# BattleBits_V2_routed.net
KiCad netlist of a schematic drawn in EAGLE
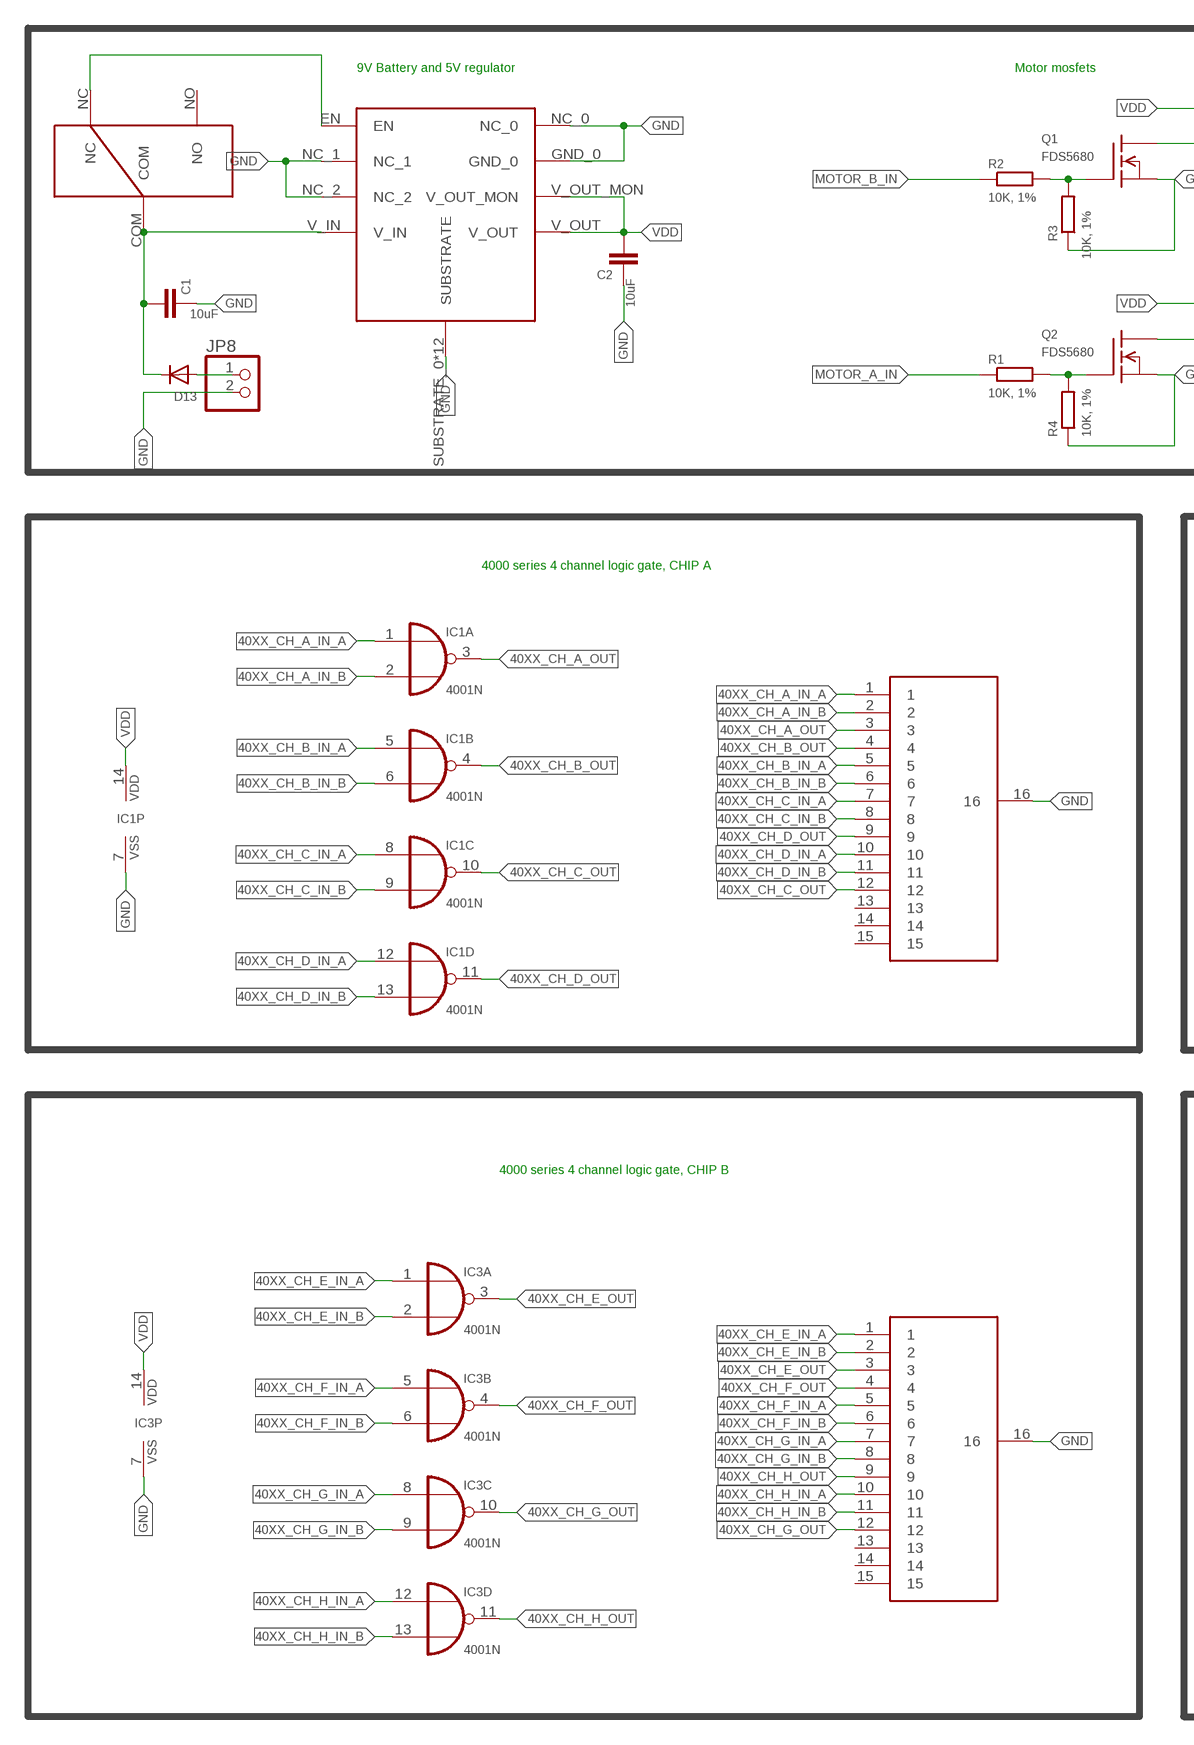
[diagram p0: schematic, sheet 1, part 1 of 2]
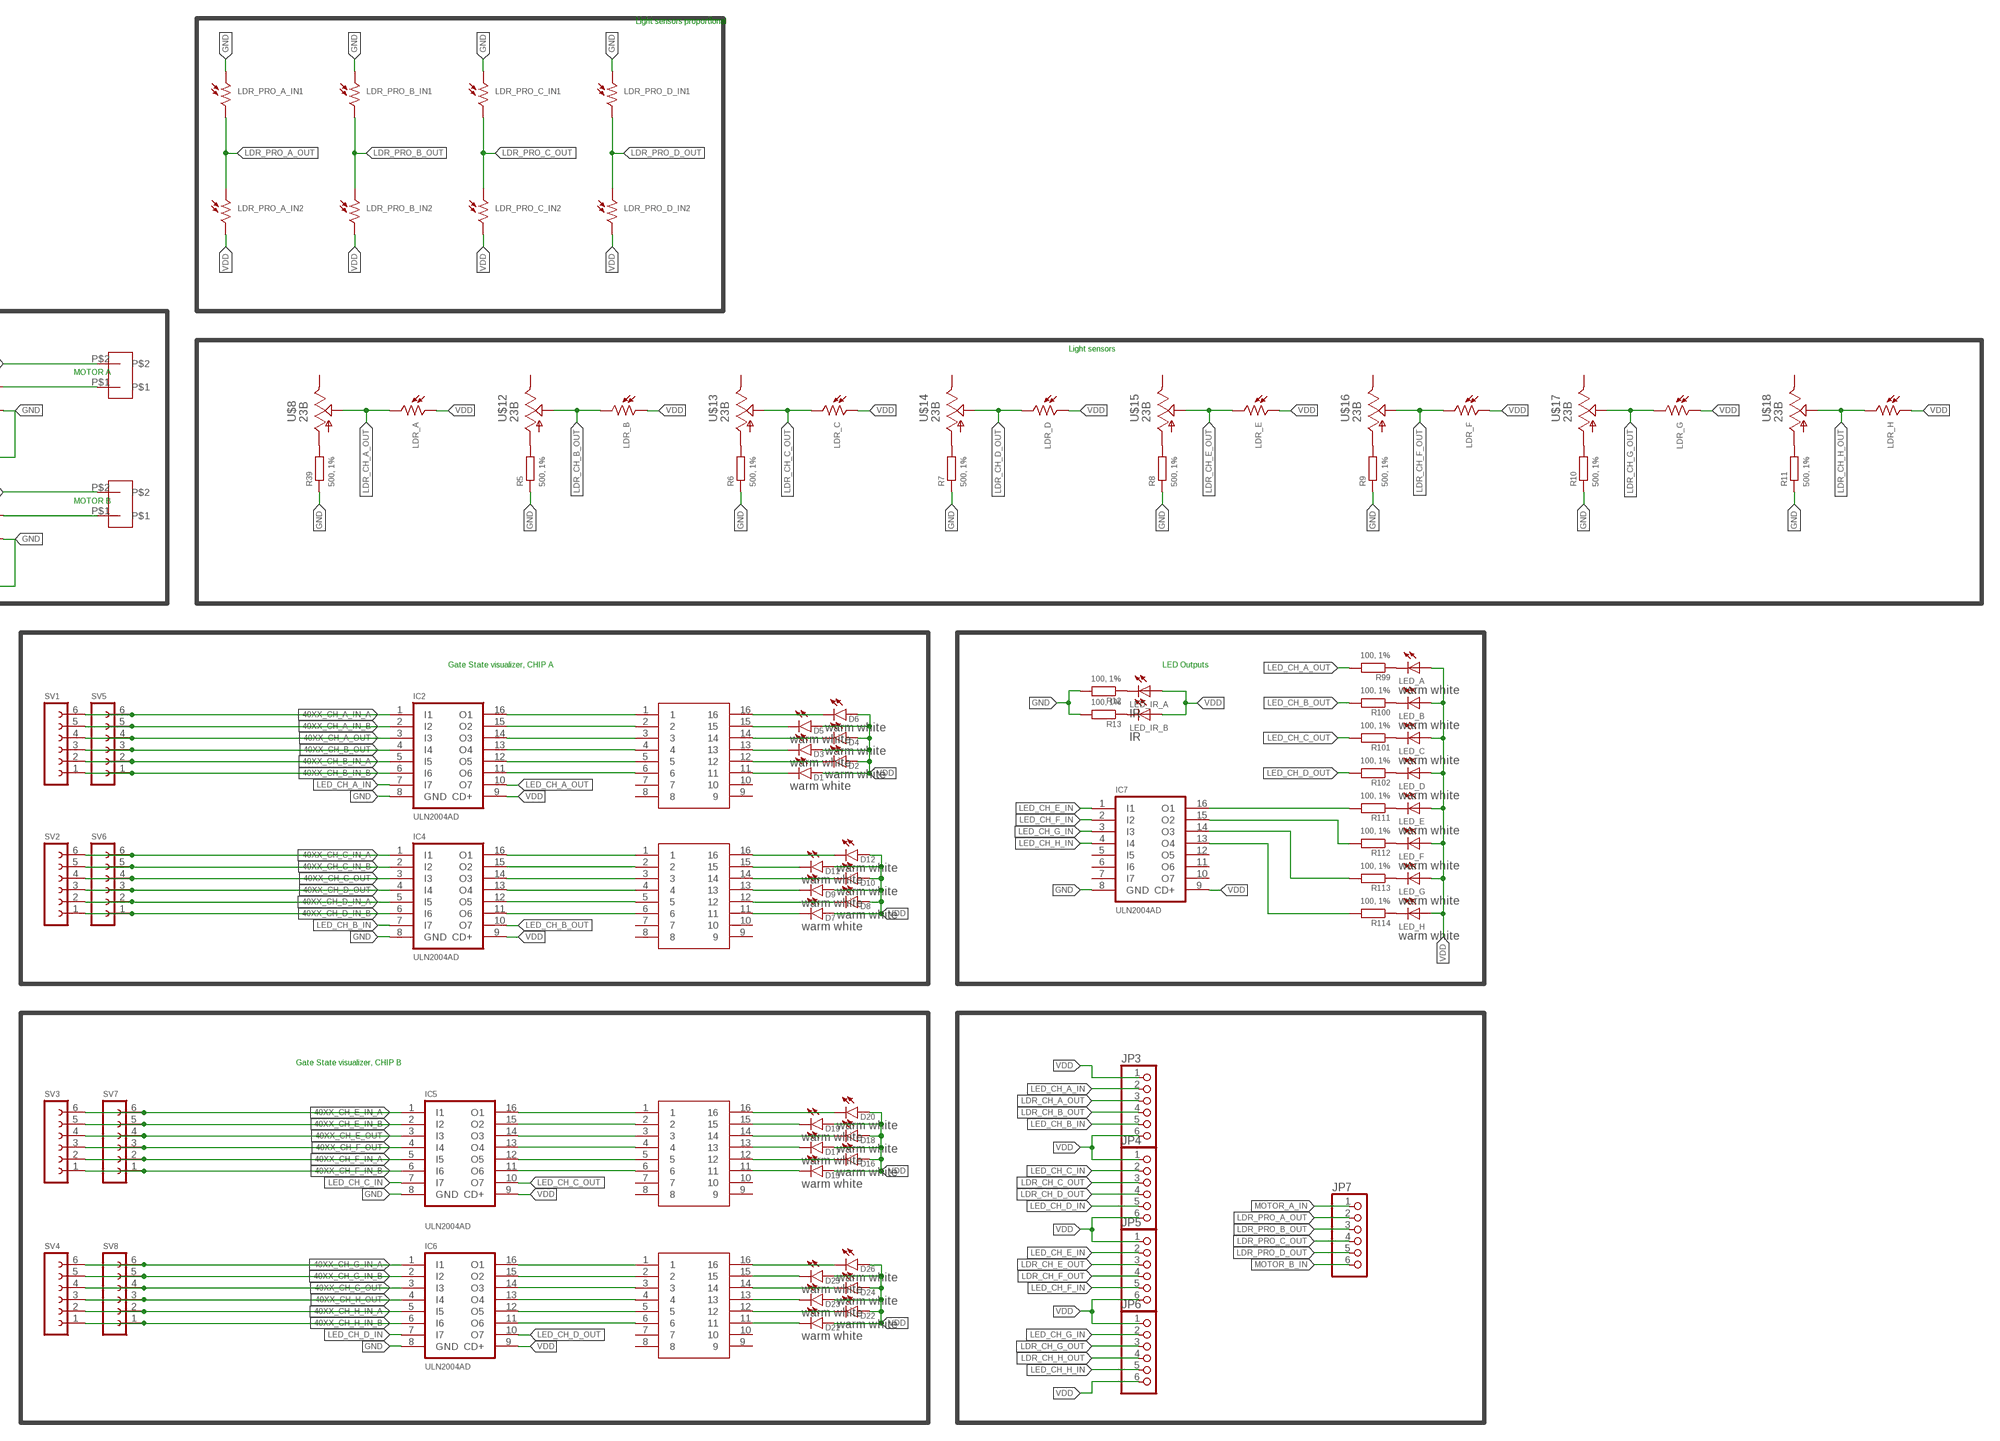
[diagram p1: schematic, sheet 1, part 2 of 2]

(export (version "E")
  (design (tool "Eeschema 10.0.6"))
  (components
    (comp (ref "C1")
      (value "10uF")
      (footprint "eagle-import:C3216")
      (libsource (lib "eagle-import") (part "C-EUC3216"))
    )
    (comp (ref "C2")
      (value "10uF")
      (footprint "eagle-import:C3216")
      (libsource (lib "eagle-import") (part "C-EUC3216"))
    )
    (comp (ref "D1")
      (value "warm white")
      (footprint "eagle-import:LED-1206")
      (libsource (lib "eagle-import") (part "LED1206"))
    )
    (comp (ref "D2")
      (value "warm white")
      (footprint "eagle-import:LED-1206")
      (libsource (lib "eagle-import") (part "LED1206"))
    )
    (comp (ref "D3")
      (value "warm white")
      (footprint "eagle-import:LED-1206")
      (libsource (lib "eagle-import") (part "LED1206"))
    )
    (comp (ref "D4")
      (value "warm white")
      (footprint "eagle-import:LED-1206")
      (libsource (lib "eagle-import") (part "LED1206"))
    )
    (comp (ref "D5")
      (value "warm white")
      (footprint "eagle-import:LED-1206")
      (libsource (lib "eagle-import") (part "LED1206"))
    )
    (comp (ref "D6")
      (value "warm white")
      (footprint "eagle-import:LED-1206")
      (libsource (lib "eagle-import") (part "LED1206"))
    )
    (comp (ref "D7")
      (value "warm white")
      (footprint "eagle-import:LED-1206")
      (libsource (lib "eagle-import") (part "LED1206"))
    )
    (comp (ref "D8")
      (value "warm white")
      (footprint "eagle-import:LED-1206")
      (libsource (lib "eagle-import") (part "LED1206"))
    )
    (comp (ref "D9")
      (value "warm white")
      (footprint "eagle-import:LED-1206")
      (libsource (lib "eagle-import") (part "LED1206"))
    )
    (comp (ref "D10")
      (value "warm white")
      (footprint "eagle-import:LED-1206")
      (libsource (lib "eagle-import") (part "LED1206"))
    )
    (comp (ref "D11")
      (value "warm white")
      (footprint "eagle-import:LED-1206")
      (libsource (lib "eagle-import") (part "LED1206"))
    )
    (comp (ref "D12")
      (value "warm white")
      (footprint "eagle-import:LED-1206")
      (libsource (lib "eagle-import") (part "LED1206"))
    )
    (comp (ref "D13")
      (value "DIODESMA")
      (footprint "eagle-import:SMADIODE")
      (libsource (lib "eagle-import") (part "DIODESMA"))
    )
    (comp (ref "D15")
      (value "warm white")
      (footprint "eagle-import:LED-1206")
      (libsource (lib "eagle-import") (part "LED1206"))
    )
    (comp (ref "D16")
      (value "warm white")
      (footprint "eagle-import:LED-1206")
      (libsource (lib "eagle-import") (part "LED1206"))
    )
    (comp (ref "D17")
      (value "warm white")
      (footprint "eagle-import:LED-1206")
      (libsource (lib "eagle-import") (part "LED1206"))
    )
    (comp (ref "D18")
      (value "warm white")
      (footprint "eagle-import:LED-1206")
      (libsource (lib "eagle-import") (part "LED1206"))
    )
    (comp (ref "D19")
      (value "warm white")
      (footprint "eagle-import:LED-1206")
      (libsource (lib "eagle-import") (part "LED1206"))
    )
    (comp (ref "D20")
      (value "warm white")
      (footprint "eagle-import:LED-1206")
      (libsource (lib "eagle-import") (part "LED1206"))
    )
    (comp (ref "D21")
      (value "warm white")
      (footprint "eagle-import:LED-1206")
      (libsource (lib "eagle-import") (part "LED1206"))
    )
    (comp (ref "D22")
      (value "warm white")
      (footprint "eagle-import:LED-1206")
      (libsource (lib "eagle-import") (part "LED1206"))
    )
    (comp (ref "D23")
      (value "warm white")
      (footprint "eagle-import:LED-1206")
      (libsource (lib "eagle-import") (part "LED1206"))
    )
    (comp (ref "D24")
      (value "warm white")
      (footprint "eagle-import:LED-1206")
      (libsource (lib "eagle-import") (part "LED1206"))
    )
    (comp (ref "D25")
      (value "warm white")
      (footprint "eagle-import:LED-1206")
      (libsource (lib "eagle-import") (part "LED1206"))
    )
    (comp (ref "D26")
      (value "warm white")
      (footprint "eagle-import:LED-1206")
      (libsource (lib "eagle-import") (part "LED1206"))
    )
    (comp (ref "IC1")
      (value "4001N")
      (footprint "eagle-import:DIL14")
      (libsource (lib "eagle-import") (part "4001N"))
    )
    (comp (ref "IC2")
      (value "ULN2004AD")
      (footprint "eagle-import:SO16")
      (libsource (lib "eagle-import") (part "ULN2004AD"))
    )
    (comp (ref "IC3")
      (value "4001N")
      (footprint "eagle-import:DIL14")
      (libsource (lib "eagle-import") (part "4001N"))
    )
    (comp (ref "IC4")
      (value "ULN2004AD")
      (footprint "eagle-import:SO16")
      (libsource (lib "eagle-import") (part "ULN2004AD"))
    )
    (comp (ref "IC5")
      (value "ULN2004AD")
      (footprint "eagle-import:SO16")
      (libsource (lib "eagle-import") (part "ULN2004AD"))
    )
    (comp (ref "IC6")
      (value "ULN2004AD")
      (footprint "eagle-import:SO16")
      (libsource (lib "eagle-import") (part "ULN2004AD"))
    )
    (comp (ref "IC7")
      (value "ULN2004AD")
      (footprint "eagle-import:SO16")
      (libsource (lib "eagle-import") (part "ULN2004AD"))
    )
    (comp (ref "JP3")
      (value "PINHD-1X6")
      (footprint "eagle-import:1X06")
      (libsource (lib "eagle-import") (part "PINHD-1X6"))
    )
    (comp (ref "JP4")
      (value "PINHD-1X6")
      (footprint "eagle-import:1X06")
      (libsource (lib "eagle-import") (part "PINHD-1X6"))
    )
    (comp (ref "JP5")
      (value "PINHD-1X6")
      (footprint "eagle-import:1X06")
      (libsource (lib "eagle-import") (part "PINHD-1X6"))
    )
    (comp (ref "JP6")
      (value "PINHD-1X6")
      (footprint "eagle-import:1X06")
      (libsource (lib "eagle-import") (part "PINHD-1X6"))
    )
    (comp (ref "JP7")
      (value "PINHD-1X6")
      (footprint "eagle-import:1X06")
      (libsource (lib "eagle-import") (part "PINHD-1X6"))
    )
    (comp (ref "JP8")
      (value "PINHD-1X2")
      (footprint "eagle-import:1X02")
      (libsource (lib "eagle-import") (part "PINHD-1X2"))
    )
    (comp (ref "LDR_A")
      (value "V1060_21")
      (footprint "eagle-import:TO-5_V10")
      (libsource (lib "eagle-import") (part "?1060V_21"))
    )
    (comp (ref "LDR_B")
      (value "V1060_21")
      (footprint "eagle-import:TO-5_V10")
      (libsource (lib "eagle-import") (part "?1060V_21"))
    )
    (comp (ref "LDR_C")
      (value "V1060_21")
      (footprint "eagle-import:TO-5_V10")
      (libsource (lib "eagle-import") (part "?1060V_21"))
    )
    (comp (ref "LDR_D")
      (value "V1060_21")
      (footprint "eagle-import:TO-5_V10")
      (libsource (lib "eagle-import") (part "?1060V_21"))
    )
    (comp (ref "LDR_E")
      (value "V1060_21")
      (footprint "eagle-import:TO-5_V10")
      (libsource (lib "eagle-import") (part "?1060V_21"))
    )
    (comp (ref "LDR_F")
      (value "V1060_21")
      (footprint "eagle-import:TO-5_V10")
      (libsource (lib "eagle-import") (part "?1060V_21"))
    )
    (comp (ref "LDR_G")
      (value "V1060_21")
      (footprint "eagle-import:TO-5_V10")
      (libsource (lib "eagle-import") (part "?1060V_21"))
    )
    (comp (ref "LDR_H")
      (value "V1060_21")
      (footprint "eagle-import:TO-5_V10")
      (libsource (lib "eagle-import") (part "?1060V_21"))
    )
    (comp (ref "LDR_PRO_A_IN1")
      (value "V1060_21")
      (footprint "eagle-import:TO-5_V10")
      (libsource (lib "eagle-import") (part "?1060V_21"))
    )
    (comp (ref "LDR_PRO_A_IN2")
      (value "V1060_21")
      (footprint "eagle-import:TO-5_V10")
      (libsource (lib "eagle-import") (part "?1060V_21"))
    )
    (comp (ref "LDR_PRO_B_IN1")
      (value "V1060_21")
      (footprint "eagle-import:TO-5_V10")
      (libsource (lib "eagle-import") (part "?1060V_21"))
    )
    (comp (ref "LDR_PRO_B_IN2")
      (value "V1060_21")
      (footprint "eagle-import:TO-5_V10")
      (libsource (lib "eagle-import") (part "?1060V_21"))
    )
    (comp (ref "LDR_PRO_C_IN1")
      (value "V1060_21")
      (footprint "eagle-import:TO-5_V10")
      (libsource (lib "eagle-import") (part "?1060V_21"))
    )
    (comp (ref "LDR_PRO_C_IN2")
      (value "V1060_21")
      (footprint "eagle-import:TO-5_V10")
      (libsource (lib "eagle-import") (part "?1060V_21"))
    )
    (comp (ref "LDR_PRO_D_IN1")
      (value "V1060_21")
      (footprint "eagle-import:TO-5_V10")
      (libsource (lib "eagle-import") (part "?1060V_21"))
    )
    (comp (ref "LDR_PRO_D_IN2")
      (value "V1060_21")
      (footprint "eagle-import:TO-5_V10")
      (libsource (lib "eagle-import") (part "?1060V_21"))
    )
    (comp (ref "LED_A")
      (value "warm white")
      (footprint "eagle-import:LED5MM")
      (libsource (lib "eagle-import") (part "adafruit_420_LED5MM"))
    )
    (comp (ref "LED_B")
      (value "warm white")
      (footprint "eagle-import:LED5MM")
      (libsource (lib "eagle-import") (part "adafruit_420_LED5MM"))
    )
    (comp (ref "LED_C")
      (value "warm white")
      (footprint "eagle-import:LED5MM")
      (libsource (lib "eagle-import") (part "adafruit_420_LED5MM"))
    )
    (comp (ref "LED_D")
      (value "warm white")
      (footprint "eagle-import:LED5MM")
      (libsource (lib "eagle-import") (part "adafruit_420_LED5MM"))
    )
    (comp (ref "LED_E")
      (value "warm white")
      (footprint "eagle-import:LED5MM")
      (libsource (lib "eagle-import") (part "adafruit_420_LED5MM"))
    )
    (comp (ref "LED_F")
      (value "warm white")
      (footprint "eagle-import:LED5MM")
      (libsource (lib "eagle-import") (part "adafruit_420_LED5MM"))
    )
    (comp (ref "LED_G")
      (value "warm white")
      (footprint "eagle-import:LED5MM")
      (libsource (lib "eagle-import") (part "adafruit_420_LED5MM"))
    )
    (comp (ref "LED_H")
      (value "warm white")
      (footprint "eagle-import:LED5MM")
      (libsource (lib "eagle-import") (part "adafruit_420_LED5MM"))
    )
    (comp (ref "LED_IR_A")
      (value "IR")
      (footprint "eagle-import:LED5MM")
      (libsource (lib "eagle-import") (part "adafruit_420_LED5MM"))
    )
    (comp (ref "LED_IR_B")
      (value "IR")
      (footprint "eagle-import:LED5MM")
      (libsource (lib "eagle-import") (part "adafruit_420_LED5MM"))
    )
    (comp (ref "Q1")
      (value "FDS5680")
      (footprint "eagle-import:SO-8")
      (libsource (lib "eagle-import") (part "FDS5680"))
    )
    (comp (ref "Q2")
      (value "FDS5680")
      (footprint "eagle-import:SO-8")
      (libsource (lib "eagle-import") (part "FDS5680"))
    )
    (comp (ref "R1")
      (value "10K, 1%")
      (footprint "eagle-import:R3216")
      (libsource (lib "eagle-import") (part "R-EU_R3216"))
    )
    (comp (ref "R2")
      (value "10K, 1%")
      (footprint "eagle-import:R3216")
      (libsource (lib "eagle-import") (part "R-EU_R3216"))
    )
    (comp (ref "R3")
      (value "10K, 1%")
      (footprint "eagle-import:R3216")
      (libsource (lib "eagle-import") (part "R-EU_R3216"))
    )
    (comp (ref "R4")
      (value "10K, 1%")
      (footprint "eagle-import:R3216")
      (libsource (lib "eagle-import") (part "R-EU_R3216"))
    )
    (comp (ref "R5")
      (value "500, 1%")
      (footprint "eagle-import:R3216")
      (libsource (lib "eagle-import") (part "R-EU_R3216"))
    )
    (comp (ref "R6")
      (value "500, 1%")
      (footprint "eagle-import:R3216")
      (libsource (lib "eagle-import") (part "R-EU_R3216"))
    )
    (comp (ref "R7")
      (value "500, 1%")
      (footprint "eagle-import:R3216")
      (libsource (lib "eagle-import") (part "R-EU_R3216"))
    )
    (comp (ref "R8")
      (value "500, 1%")
      (footprint "eagle-import:R3216")
      (libsource (lib "eagle-import") (part "R-EU_R3216"))
    )
    (comp (ref "R9")
      (value "500, 1%")
      (footprint "eagle-import:R3216")
      (libsource (lib "eagle-import") (part "R-EU_R3216"))
    )
    (comp (ref "R10")
      (value "500, 1%")
      (footprint "eagle-import:R3216")
      (libsource (lib "eagle-import") (part "R-EU_R3216"))
    )
    (comp (ref "R11")
      (value "500, 1%")
      (footprint "eagle-import:R3216")
      (libsource (lib "eagle-import") (part "R-EU_R3216"))
    )
    (comp (ref "R12")
      (value "100, 1%")
      (footprint "eagle-import:R3216")
      (libsource (lib "eagle-import") (part "R-EU_R3216"))
    )
    (comp (ref "R13")
      (value "100, 1%")
      (footprint "eagle-import:R3216")
      (libsource (lib "eagle-import") (part "R-EU_R3216"))
    )
    (comp (ref "R39")
      (value "500, 1%")
      (footprint "eagle-import:R3216")
      (libsource (lib "eagle-import") (part "R-EU_R3216"))
    )
    (comp (ref "R99")
      (value "100, 1%")
      (footprint "eagle-import:R3216")
      (libsource (lib "eagle-import") (part "R-EU_R3216"))
    )
    (comp (ref "R100")
      (value "100, 1%")
      (footprint "eagle-import:R3216")
      (libsource (lib "eagle-import") (part "R-EU_R3216"))
    )
    (comp (ref "R101")
      (value "100, 1%")
      (footprint "eagle-import:R3216")
      (libsource (lib "eagle-import") (part "R-EU_R3216"))
    )
    (comp (ref "R102")
      (value "100, 1%")
      (footprint "eagle-import:R3216")
      (libsource (lib "eagle-import") (part "R-EU_R3216"))
    )
    (comp (ref "R111")
      (value "100, 1%")
      (footprint "eagle-import:R3216")
      (libsource (lib "eagle-import") (part "R-EU_R3216"))
    )
    (comp (ref "R112")
      (value "100, 1%")
      (footprint "eagle-import:R3216")
      (libsource (lib "eagle-import") (part "R-EU_R3216"))
    )
    (comp (ref "R113")
      (value "100, 1%")
      (footprint "eagle-import:R3216")
      (libsource (lib "eagle-import") (part "R-EU_R3216"))
    )
    (comp (ref "R114")
      (value "100, 1%")
      (footprint "eagle-import:R3216")
      (libsource (lib "eagle-import") (part "R-EU_R3216"))
    )
    (comp (ref "SV1")
      (value "FE06-1")
      (footprint "eagle-import:FE06")
      (libsource (lib "eagle-import") (part "FE06-1"))
    )
    (comp (ref "SV2")
      (value "FE06-1")
      (footprint "eagle-import:FE06")
      (libsource (lib "eagle-import") (part "FE06-1"))
    )
    (comp (ref "SV3")
      (value "FE06-1")
      (footprint "eagle-import:FE06")
      (libsource (lib "eagle-import") (part "FE06-1"))
    )
    (comp (ref "SV4")
      (value "FE06-1")
      (footprint "eagle-import:FE06")
      (libsource (lib "eagle-import") (part "FE06-1"))
    )
    (comp (ref "SV5")
      (value "FE06-1")
      (footprint "eagle-import:FE06")
      (libsource (lib "eagle-import") (part "FE06-1"))
    )
    (comp (ref "SV6")
      (value "FE06-1")
      (footprint "eagle-import:FE06")
      (libsource (lib "eagle-import") (part "FE06-1"))
    )
    (comp (ref "SV7")
      (value "FE06-1")
      (footprint "eagle-import:FE06")
      (libsource (lib "eagle-import") (part "FE06-1"))
    )
    (comp (ref "SV8")
      (value "FE06-1")
      (footprint "eagle-import:FE06")
      (libsource (lib "eagle-import") (part "FE06-1"))
    )
    (comp (ref "U$1")
      (value "MOTOR")
      (footprint "eagle-import:GEARMOTOR")
      (libsource (lib "eagle-import") (part "MOTOR"))
    )
    (comp (ref "U$2")
      (value "MOTOR")
      (footprint "eagle-import:GEARMOTOR")
      (libsource (lib "eagle-import") (part "MOTOR"))
    )
    (comp (ref "U$3")
      (value "15_RES_BUS_SOIC16")
      (footprint "eagle-import:SO16")
      (libsource (lib "eagle-import") (part "15_RES_BUS_SOIC16"))
    )
    (comp (ref "U$4")
      (value "ROHM_LDO")
      (footprint "eagle-import:HTSOP-J8")
      (libsource (lib "eagle-import") (part "ROHM_LDO"))
    )
    (comp (ref "U$5")
      (value "8_RES_ISO_SOIC-16")
      (footprint "eagle-import:SO16")
      (libsource (lib "eagle-import") (part "8_RES_ISO_SOIC-16"))
    )
    (comp (ref "U$6")
      (value "8_RES_ISO_SOIC-16")
      (footprint "eagle-import:SO16")
      (libsource (lib "eagle-import") (part "8_RES_ISO_SOIC-16"))
    )
    (comp (ref "U$7")
      (value "SLIDE_SWITCH")
      (footprint "eagle-import:SLIDE_SWITCH")
      (libsource (lib "eagle-import") (part "SLIDE_SWITCH"))
    )
    (comp (ref "U$8")
      (value "23B")
      (footprint "eagle-import:23B-GULL_WING")
      (libsource (lib "eagle-import") (part "23B"))
    )
    (comp (ref "U$9")
      (value "8_RES_ISO_SOIC-16")
      (footprint "eagle-import:SO16")
      (libsource (lib "eagle-import") (part "8_RES_ISO_SOIC-16"))
    )
    (comp (ref "U$10")
      (value "8_RES_ISO_SOIC-16")
      (footprint "eagle-import:SO16")
      (libsource (lib "eagle-import") (part "8_RES_ISO_SOIC-16"))
    )
    (comp (ref "U$11")
      (value "15_RES_BUS_SOIC16")
      (footprint "eagle-import:SO16")
      (libsource (lib "eagle-import") (part "15_RES_BUS_SOIC16"))
    )
    (comp (ref "U$12")
      (value "23B")
      (footprint "eagle-import:23B-GULL_WING")
      (libsource (lib "eagle-import") (part "23B"))
    )
    (comp (ref "U$13")
      (value "23B")
      (footprint "eagle-import:23B-GULL_WING")
      (libsource (lib "eagle-import") (part "23B"))
    )
    (comp (ref "U$14")
      (value "23B")
      (footprint "eagle-import:23B-GULL_WING")
      (libsource (lib "eagle-import") (part "23B"))
    )
    (comp (ref "U$15")
      (value "23B")
      (footprint "eagle-import:23B-GULL_WING")
      (libsource (lib "eagle-import") (part "23B"))
    )
    (comp (ref "U$16")
      (value "23B")
      (footprint "eagle-import:23B-GULL_WING")
      (libsource (lib "eagle-import") (part "23B"))
    )
    (comp (ref "U$17")
      (value "23B")
      (footprint "eagle-import:23B-GULL_WING")
      (libsource (lib "eagle-import") (part "23B"))
    )
    (comp (ref "U$18")
      (value "23B")
      (footprint "eagle-import:23B-GULL_WING")
      (libsource (lib "eagle-import") (part "23B"))
    )
  )
  (nets
    (net (code "1") (name "40XX_CH_A_IN_A") (class "Default")
      (node (ref "IC1") (pin "1") (pinfunction "I0_1") (pintype "input"))
      (node (ref "IC2") (pin "1") (pinfunction "I1_1") (pintype "input"))
      (node (ref "SV1") (pin "6") (pinfunction "6_6") (pintype "passive"))
      (node (ref "SV5") (pin "6") (pinfunction "6_6") (pintype "passive"))
      (node (ref "U$11") (pin "1") (pinfunction "1_1") (pintype "bidirectional"))
    )
    (net (code "2") (name "40XX_CH_A_IN_B") (class "Default")
      (node (ref "IC1") (pin "2") (pinfunction "I1_2") (pintype "input"))
      (node (ref "IC2") (pin "2") (pinfunction "I2_2") (pintype "input"))
      (node (ref "SV1") (pin "5") (pinfunction "5_5") (pintype "passive"))
      (node (ref "SV5") (pin "5") (pinfunction "5_5") (pintype "passive"))
      (node (ref "U$11") (pin "2") (pinfunction "2_2") (pintype "bidirectional"))
    )
    (net (code "3") (name "40XX_CH_A_OUT") (class "Default")
      (node (ref "IC1") (pin "3") (pinfunction "O_3") (pintype "output"))
      (node (ref "IC2") (pin "3") (pinfunction "I3_3") (pintype "input"))
      (node (ref "SV1") (pin "4") (pinfunction "4_4") (pintype "passive"))
      (node (ref "SV5") (pin "4") (pinfunction "4_4") (pintype "passive"))
      (node (ref "U$11") (pin "3") (pinfunction "3_3") (pintype "bidirectional"))
    )
    (net (code "4") (name "40XX_CH_B_IN_A") (class "Default")
      (node (ref "IC1") (pin "5") (pinfunction "I0_5") (pintype "input"))
      (node (ref "IC2") (pin "5") (pinfunction "I5_5") (pintype "input"))
      (node (ref "SV1") (pin "2") (pinfunction "2_2") (pintype "passive"))
      (node (ref "SV5") (pin "2") (pinfunction "2_2") (pintype "passive"))
      (node (ref "U$11") (pin "5") (pinfunction "5_5") (pintype "bidirectional"))
    )
    (net (code "5") (name "40XX_CH_B_IN_B") (class "Default")
      (node (ref "IC1") (pin "6") (pinfunction "I1_6") (pintype "input"))
      (node (ref "IC2") (pin "6") (pinfunction "I6_6") (pintype "input"))
      (node (ref "SV1") (pin "1") (pinfunction "1_1") (pintype "passive"))
      (node (ref "SV5") (pin "1") (pinfunction "1_1") (pintype "passive"))
      (node (ref "U$11") (pin "6") (pinfunction "6_6") (pintype "bidirectional"))
    )
    (net (code "6") (name "40XX_CH_B_OUT") (class "Default")
      (node (ref "IC1") (pin "4") (pinfunction "O_4") (pintype "output"))
      (node (ref "IC2") (pin "4") (pinfunction "I4_4") (pintype "input"))
      (node (ref "SV1") (pin "3") (pinfunction "3_3") (pintype "passive"))
      (node (ref "SV5") (pin "3") (pinfunction "3_3") (pintype "passive"))
      (node (ref "U$11") (pin "4") (pinfunction "4_4") (pintype "bidirectional"))
    )
    (net (code "7") (name "40XX_CH_C_IN_A") (class "Default")
      (node (ref "IC1") (pin "8") (pinfunction "I0_8") (pintype "input"))
      (node (ref "IC4") (pin "1") (pinfunction "I1_1") (pintype "input"))
      (node (ref "SV2") (pin "6") (pinfunction "6_6") (pintype "passive"))
      (node (ref "SV6") (pin "6") (pinfunction "6_6") (pintype "passive"))
      (node (ref "U$11") (pin "7") (pinfunction "7_7") (pintype "bidirectional"))
    )
    (net (code "8") (name "40XX_CH_C_IN_B") (class "Default")
      (node (ref "IC1") (pin "9") (pinfunction "I1_9") (pintype "input"))
      (node (ref "IC4") (pin "2") (pinfunction "I2_2") (pintype "input"))
      (node (ref "SV2") (pin "5") (pinfunction "5_5") (pintype "passive"))
      (node (ref "SV6") (pin "5") (pinfunction "5_5") (pintype "passive"))
      (node (ref "U$11") (pin "8") (pinfunction "8_8") (pintype "bidirectional"))
    )
    (net (code "9") (name "40XX_CH_C_OUT") (class "Default")
      (node (ref "IC1") (pin "10") (pinfunction "O_10") (pintype "output"))
      (node (ref "IC4") (pin "3") (pinfunction "I3_3") (pintype "input"))
      (node (ref "SV2") (pin "4") (pinfunction "4_4") (pintype "passive"))
      (node (ref "SV6") (pin "4") (pinfunction "4_4") (pintype "passive"))
      (node (ref "U$11") (pin "12") (pinfunction "12_12") (pintype "bidirectional"))
    )
    (net (code "10") (name "40XX_CH_D_IN_A") (class "Default")
      (node (ref "IC1") (pin "12") (pinfunction "I0_12") (pintype "input"))
      (node (ref "IC4") (pin "5") (pinfunction "I5_5") (pintype "input"))
      (node (ref "SV2") (pin "2") (pinfunction "2_2") (pintype "passive"))
      (node (ref "SV6") (pin "2") (pinfunction "2_2") (pintype "passive"))
      (node (ref "U$11") (pin "10") (pinfunction "10_10") (pintype "bidirectional"))
    )
    (net (code "11") (name "40XX_CH_D_IN_B") (class "Default")
      (node (ref "IC1") (pin "13") (pinfunction "I1_13") (pintype "input"))
      (node (ref "IC4") (pin "6") (pinfunction "I6_6") (pintype "input"))
      (node (ref "SV2") (pin "1") (pinfunction "1_1") (pintype "passive"))
      (node (ref "SV6") (pin "1") (pinfunction "1_1") (pintype "passive"))
      (node (ref "U$11") (pin "11") (pinfunction "11_11") (pintype "bidirectional"))
    )
    (net (code "12") (name "40XX_CH_D_OUT") (class "Default")
      (node (ref "IC1") (pin "11") (pinfunction "O_11") (pintype "output"))
      (node (ref "IC4") (pin "4") (pinfunction "I4_4") (pintype "input"))
      (node (ref "SV2") (pin "3") (pinfunction "3_3") (pintype "passive"))
      (node (ref "SV6") (pin "3") (pinfunction "3_3") (pintype "passive"))
      (node (ref "U$11") (pin "9") (pinfunction "9_9") (pintype "bidirectional"))
    )
    (net (code "13") (name "40XX_CH_E_IN_A") (class "Default")
      (node (ref "IC3") (pin "1") (pinfunction "I0_1") (pintype "input"))
      (node (ref "IC5") (pin "1") (pinfunction "I1_1") (pintype "input"))
      (node (ref "SV3") (pin "6") (pinfunction "6_6") (pintype "passive"))
      (node (ref "SV7") (pin "6") (pinfunction "6_6") (pintype "passive"))
      (node (ref "U$3") (pin "1") (pinfunction "1_1") (pintype "bidirectional"))
    )
    (net (code "14") (name "40XX_CH_E_IN_B") (class "Default")
      (node (ref "IC3") (pin "2") (pinfunction "I1_2") (pintype "input"))
      (node (ref "IC5") (pin "2") (pinfunction "I2_2") (pintype "input"))
      (node (ref "SV3") (pin "5") (pinfunction "5_5") (pintype "passive"))
      (node (ref "SV7") (pin "5") (pinfunction "5_5") (pintype "passive"))
      (node (ref "U$3") (pin "2") (pinfunction "2_2") (pintype "bidirectional"))
    )
    (net (code "15") (name "40XX_CH_E_OUT") (class "Default")
      (node (ref "IC3") (pin "3") (pinfunction "O_3") (pintype "output"))
      (node (ref "IC5") (pin "3") (pinfunction "I3_3") (pintype "input"))
      (node (ref "SV3") (pin "4") (pinfunction "4_4") (pintype "passive"))
      (node (ref "SV7") (pin "4") (pinfunction "4_4") (pintype "passive"))
      (node (ref "U$3") (pin "3") (pinfunction "3_3") (pintype "bidirectional"))
    )
    (net (code "16") (name "40XX_CH_F_IN_A") (class "Default")
      (node (ref "IC3") (pin "5") (pinfunction "I0_5") (pintype "input"))
      (node (ref "IC5") (pin "5") (pinfunction "I5_5") (pintype "input"))
      (node (ref "SV3") (pin "2") (pinfunction "2_2") (pintype "passive"))
      (node (ref "SV7") (pin "2") (pinfunction "2_2") (pintype "passive"))
      (node (ref "U$3") (pin "5") (pinfunction "5_5") (pintype "bidirectional"))
    )
    (net (code "17") (name "40XX_CH_F_IN_B") (class "Default")
      (node (ref "IC3") (pin "6") (pinfunction "I1_6") (pintype "input"))
      (node (ref "IC5") (pin "6") (pinfunction "I6_6") (pintype "input"))
      (node (ref "SV3") (pin "1") (pinfunction "1_1") (pintype "passive"))
      (node (ref "SV7") (pin "1") (pinfunction "1_1") (pintype "passive"))
      (node (ref "U$3") (pin "6") (pinfunction "6_6") (pintype "bidirectional"))
    )
    (net (code "18") (name "40XX_CH_F_OUT") (class "Default")
      (node (ref "IC3") (pin "4") (pinfunction "O_4") (pintype "output"))
      (node (ref "IC5") (pin "4") (pinfunction "I4_4") (pintype "input"))
      (node (ref "SV3") (pin "3") (pinfunction "3_3") (pintype "passive"))
      (node (ref "SV7") (pin "3") (pinfunction "3_3") (pintype "passive"))
      (node (ref "U$3") (pin "4") (pinfunction "4_4") (pintype "bidirectional"))
    )
    (net (code "19") (name "40XX_CH_G_IN_A") (class "Default")
      (node (ref "IC3") (pin "8") (pinfunction "I0_8") (pintype "input"))
      (node (ref "IC6") (pin "1") (pinfunction "I1_1") (pintype "input"))
      (node (ref "SV4") (pin "6") (pinfunction "6_6") (pintype "passive"))
      (node (ref "SV8") (pin "6") (pinfunction "6_6") (pintype "passive"))
      (node (ref "U$3") (pin "7") (pinfunction "7_7") (pintype "bidirectional"))
    )
    (net (code "20") (name "40XX_CH_G_IN_B") (class "Default")
      (node (ref "IC3") (pin "9") (pinfunction "I1_9") (pintype "input"))
      (node (ref "IC6") (pin "2") (pinfunction "I2_2") (pintype "input"))
      (node (ref "SV4") (pin "5") (pinfunction "5_5") (pintype "passive"))
      (node (ref "SV8") (pin "5") (pinfunction "5_5") (pintype "passive"))
      (node (ref "U$3") (pin "8") (pinfunction "8_8") (pintype "bidirectional"))
    )
    (net (code "21") (name "40XX_CH_G_OUT") (class "Default")
      (node (ref "IC3") (pin "10") (pinfunction "O_10") (pintype "output"))
      (node (ref "IC6") (pin "3") (pinfunction "I3_3") (pintype "input"))
      (node (ref "SV4") (pin "4") (pinfunction "4_4") (pintype "passive"))
      (node (ref "SV8") (pin "4") (pinfunction "4_4") (pintype "passive"))
      (node (ref "U$3") (pin "12") (pinfunction "12_12") (pintype "bidirectional"))
    )
    (net (code "22") (name "40XX_CH_H_IN_A") (class "Default")
      (node (ref "IC3") (pin "12") (pinfunction "I0_12") (pintype "input"))
      (node (ref "IC6") (pin "5") (pinfunction "I5_5") (pintype "input"))
      (node (ref "SV4") (pin "2") (pinfunction "2_2") (pintype "passive"))
      (node (ref "SV8") (pin "2") (pinfunction "2_2") (pintype "passive"))
      (node (ref "U$3") (pin "10") (pinfunction "10_10") (pintype "bidirectional"))
    )
    (net (code "23") (name "40XX_CH_H_IN_B") (class "Default")
      (node (ref "IC3") (pin "13") (pinfunction "I1_13") (pintype "input"))
      (node (ref "IC6") (pin "6") (pinfunction "I6_6") (pintype "input"))
      (node (ref "SV4") (pin "1") (pinfunction "1_1") (pintype "passive"))
      (node (ref "SV8") (pin "1") (pinfunction "1_1") (pintype "passive"))
      (node (ref "U$3") (pin "11") (pinfunction "11_11") (pintype "bidirectional"))
    )
    (net (code "24") (name "40XX_CH_H_OUT") (class "Default")
      (node (ref "IC3") (pin "11") (pinfunction "O_11") (pintype "output"))
      (node (ref "IC6") (pin "4") (pinfunction "I4_4") (pintype "input"))
      (node (ref "SV4") (pin "3") (pinfunction "3_3") (pintype "passive"))
      (node (ref "SV8") (pin "3") (pinfunction "3_3") (pintype "passive"))
      (node (ref "U$3") (pin "9") (pinfunction "9_9") (pintype "bidirectional"))
    )
    (net (code "25") (name "GND") (class "Default")
      (node (ref "C1") (pin "1") (pinfunction "1_1") (pintype "passive"))
      (node (ref "C2") (pin "1") (pinfunction "1_1") (pintype "passive"))
      (node (ref "IC1") (pin "7") (pinfunction "VSS_7") (pintype "power_in"))
      (node (ref "IC2") (pin "8") (pinfunction "GND_8") (pintype "power_in"))
      (node (ref "IC3") (pin "7") (pinfunction "VSS_7") (pintype "power_in"))
      (node (ref "IC4") (pin "8") (pinfunction "GND_8") (pintype "power_in"))
      (node (ref "IC5") (pin "8") (pinfunction "GND_8") (pintype "power_in"))
      (node (ref "IC6") (pin "8") (pinfunction "GND_8") (pintype "power_in"))
      (node (ref "IC7") (pin "8") (pinfunction "GND_8") (pintype "power_in"))
      (node (ref "JP8") (pin "2") (pinfunction "2_2") (pintype "passive"))
      (node (ref "LDR_PRO_A_IN1") (pin "1") (pinfunction "1_1") (pintype "passive"))
      (node (ref "LDR_PRO_B_IN1") (pin "1") (pinfunction "1_1") (pintype "passive"))
      (node (ref "LDR_PRO_C_IN1") (pin "1") (pinfunction "1_1") (pintype "passive"))
      (node (ref "LDR_PRO_D_IN1") (pin "1") (pinfunction "1_1") (pintype "passive"))
      (node (ref "Q1") (pin "1") (pinfunction "S_1") (pintype "passive"))
      (node (ref "Q1") (pin "2") (pinfunction "S_2") (pintype "passive"))
      (node (ref "Q1") (pin "3") (pinfunction "S_3") (pintype "passive"))
      (node (ref "Q2") (pin "1") (pinfunction "S_1") (pintype "passive"))
      (node (ref "Q2") (pin "2") (pinfunction "S_2") (pintype "passive"))
      (node (ref "Q2") (pin "3") (pinfunction "S_3") (pintype "passive"))
      (node (ref "R10") (pin "1") (pinfunction "1_1") (pintype "passive"))
      (node (ref "R11") (pin "1") (pinfunction "1_1") (pintype "passive"))
      (node (ref "R12") (pin "2") (pinfunction "2_2") (pintype "passive"))
      (node (ref "R13") (pin "2") (pinfunction "2_2") (pintype "passive"))
      (node (ref "R3") (pin "1") (pinfunction "1_1") (pintype "passive"))
      (node (ref "R39") (pin "1") (pinfunction "1_1") (pintype "passive"))
      (node (ref "R4") (pin "1") (pinfunction "1_1") (pintype "passive"))
      (node (ref "R5") (pin "1") (pinfunction "1_1") (pintype "passive"))
      (node (ref "R6") (pin "1") (pinfunction "1_1") (pintype "passive"))
      (node (ref "R7") (pin "1") (pinfunction "1_1") (pintype "passive"))
      (node (ref "R8") (pin "1") (pinfunction "1_1") (pintype "passive"))
      (node (ref "R9") (pin "1") (pinfunction "1_1") (pintype "passive"))
      (node (ref "U$11") (pin "16") (pinfunction "16_16") (pintype "bidirectional"))
      (node (ref "U$3") (pin "16") (pinfunction "16_16") (pintype "bidirectional"))
      (node (ref "U$4") (pin "GND_0") (pinfunction "GND_0_GND_0") (pintype "bidirectional"))
      (node (ref "U$4") (pin "NC_0") (pinfunction "NC_0_NC_0") (pintype "bidirectional"))
      (node (ref "U$4") (pin "NC_1") (pinfunction "NC_1_NC_1") (pintype "bidirectional"))
      (node (ref "U$4") (pin "NC_2") (pinfunction "NC_2_NC_2") (pintype "bidirectional"))
      (node (ref "U$4") (pin "SUBSTRATE_0") (pinfunction "SUBSTRATE_SUBSTRATE_0") (pintype "bidirectional"))
      (node (ref "U$4") (pin "SUBSTRATE_1") (pinfunction "SUBSTRATE_SUBSTRATE_1") (pintype "bidirectional"))
      (node (ref "U$4") (pin "SUBSTRATE_10") (pinfunction "SUBSTRATE_SUBSTRATE_10") (pintype "bidirectional"))
      (node (ref "U$4") (pin "SUBSTRATE_11") (pinfunction "SUBSTRATE_SUBSTRATE_11") (pintype "bidirectional"))
      (node (ref "U$4") (pin "SUBSTRATE_2") (pinfunction "SUBSTRATE_SUBSTRATE_2") (pintype "bidirectional"))
      (node (ref "U$4") (pin "SUBSTRATE_3") (pinfunction "SUBSTRATE_SUBSTRATE_3") (pintype "bidirectional"))
      (node (ref "U$4") (pin "SUBSTRATE_4") (pinfunction "SUBSTRATE_SUBSTRATE_4") (pintype "bidirectional"))
      (node (ref "U$4") (pin "SUBSTRATE_5") (pinfunction "SUBSTRATE_SUBSTRATE_5") (pintype "bidirectional"))
      (node (ref "U$4") (pin "SUBSTRATE_6") (pinfunction "SUBSTRATE_SUBSTRATE_6") (pintype "bidirectional"))
      (node (ref "U$4") (pin "SUBSTRATE_7") (pinfunction "SUBSTRATE_SUBSTRATE_7") (pintype "bidirectional"))
      (node (ref "U$4") (pin "SUBSTRATE_8") (pinfunction "SUBSTRATE_SUBSTRATE_8") (pintype "bidirectional"))
      (node (ref "U$4") (pin "SUBSTRATE_9") (pinfunction "SUBSTRATE_SUBSTRATE_9") (pintype "bidirectional"))
    )
    (net (code "26") (name "LDR_CH_A_OUT") (class "Default")
      (node (ref "JP3") (pin "3") (pinfunction "3_3") (pintype "passive"))
      (node (ref "LDR_A") (pin "2") (pinfunction "2_2") (pintype "passive"))
      (node (ref "U$8") (pin "2") (pinfunction "2_2") (pintype "passive"))
    )
    (net (code "27") (name "LDR_CH_B_OUT") (class "Default")
      (node (ref "JP3") (pin "4") (pinfunction "4_4") (pintype "passive"))
      (node (ref "LDR_B") (pin "2") (pinfunction "2_2") (pintype "passive"))
      (node (ref "U$12") (pin "2") (pinfunction "2_2") (pintype "passive"))
    )
    (net (code "28") (name "LDR_CH_C_OUT") (class "Default")
      (node (ref "JP4") (pin "3") (pinfunction "3_3") (pintype "passive"))
      (node (ref "LDR_C") (pin "2") (pinfunction "2_2") (pintype "passive"))
      (node (ref "U$13") (pin "2") (pinfunction "2_2") (pintype "passive"))
    )
    (net (code "29") (name "LDR_CH_D_OUT") (class "Default")
      (node (ref "JP4") (pin "4") (pinfunction "4_4") (pintype "passive"))
      (node (ref "LDR_D") (pin "2") (pinfunction "2_2") (pintype "passive"))
      (node (ref "U$14") (pin "2") (pinfunction "2_2") (pintype "passive"))
    )
    (net (code "30") (name "LDR_CH_E_OUT") (class "Default")
      (node (ref "JP5") (pin "3") (pinfunction "3_3") (pintype "passive"))
      (node (ref "LDR_E") (pin "2") (pinfunction "2_2") (pintype "passive"))
      (node (ref "U$15") (pin "2") (pinfunction "2_2") (pintype "passive"))
    )
    (net (code "31") (name "LDR_CH_F_OUT") (class "Default")
      (node (ref "JP5") (pin "4") (pinfunction "4_4") (pintype "passive"))
      (node (ref "LDR_F") (pin "2") (pinfunction "2_2") (pintype "passive"))
      (node (ref "U$16") (pin "2") (pinfunction "2_2") (pintype "passive"))
    )
    (net (code "32") (name "LDR_CH_G_OUT") (class "Default")
      (node (ref "JP6") (pin "3") (pinfunction "3_3") (pintype "passive"))
      (node (ref "LDR_G") (pin "2") (pinfunction "2_2") (pintype "passive"))
      (node (ref "U$17") (pin "2") (pinfunction "2_2") (pintype "passive"))
    )
    (net (code "33") (name "LDR_CH_H_OUT") (class "Default")
      (node (ref "JP6") (pin "4") (pinfunction "4_4") (pintype "passive"))
      (node (ref "LDR_H") (pin "2") (pinfunction "2_2") (pintype "passive"))
      (node (ref "U$18") (pin "2") (pinfunction "2_2") (pintype "passive"))
    )
    (net (code "34") (name "LDR_PRO_A_OUT") (class "Default")
      (node (ref "JP7") (pin "2") (pinfunction "2_2") (pintype "passive"))
      (node (ref "LDR_PRO_A_IN1") (pin "2") (pinfunction "2_2") (pintype "passive"))
      (node (ref "LDR_PRO_A_IN2") (pin "1") (pinfunction "1_1") (pintype "passive"))
    )
    (net (code "35") (name "LDR_PRO_B_OUT") (class "Default")
      (node (ref "JP7") (pin "3") (pinfunction "3_3") (pintype "passive"))
      (node (ref "LDR_PRO_B_IN1") (pin "2") (pinfunction "2_2") (pintype "passive"))
      (node (ref "LDR_PRO_B_IN2") (pin "1") (pinfunction "1_1") (pintype "passive"))
    )
    (net (code "36") (name "LDR_PRO_C_OUT") (class "Default")
      (node (ref "JP7") (pin "4") (pinfunction "4_4") (pintype "passive"))
      (node (ref "LDR_PRO_C_IN1") (pin "2") (pinfunction "2_2") (pintype "passive"))
      (node (ref "LDR_PRO_C_IN2") (pin "1") (pinfunction "1_1") (pintype "passive"))
    )
    (net (code "37") (name "LDR_PRO_D_OUT") (class "Default")
      (node (ref "JP7") (pin "5") (pinfunction "5_5") (pintype "passive"))
      (node (ref "LDR_PRO_D_IN1") (pin "2") (pinfunction "2_2") (pintype "passive"))
      (node (ref "LDR_PRO_D_IN2") (pin "1") (pinfunction "1_1") (pintype "passive"))
    )
    (net (code "38") (name "LED_CH_A_IN") (class "Default")
      (node (ref "IC2") (pin "7") (pinfunction "I7_7") (pintype "input"))
      (node (ref "JP3") (pin "2") (pinfunction "2_2") (pintype "passive"))
    )
    (net (code "39") (name "LED_CH_A_OUT") (class "Default")
      (node (ref "IC2") (pin "10") (pinfunction "O7_10") (pintype "open_collector"))
      (node (ref "R99") (pin "2") (pinfunction "2_2") (pintype "passive"))
    )
    (net (code "40") (name "LED_CH_B_IN") (class "Default")
      (node (ref "IC4") (pin "7") (pinfunction "I7_7") (pintype "input"))
      (node (ref "JP3") (pin "5") (pinfunction "5_5") (pintype "passive"))
    )
    (net (code "41") (name "LED_CH_B_OUT") (class "Default")
      (node (ref "IC4") (pin "10") (pinfunction "O7_10") (pintype "open_collector"))
      (node (ref "R100") (pin "2") (pinfunction "2_2") (pintype "passive"))
    )
    (net (code "42") (name "LED_CH_C_IN") (class "Default")
      (node (ref "IC5") (pin "7") (pinfunction "I7_7") (pintype "input"))
      (node (ref "JP4") (pin "2") (pinfunction "2_2") (pintype "passive"))
    )
    (net (code "43") (name "LED_CH_C_OUT") (class "Default")
      (node (ref "IC5") (pin "10") (pinfunction "O7_10") (pintype "open_collector"))
      (node (ref "R101") (pin "2") (pinfunction "2_2") (pintype "passive"))
    )
    (net (code "44") (name "LED_CH_D_IN") (class "Default")
      (node (ref "IC6") (pin "7") (pinfunction "I7_7") (pintype "input"))
      (node (ref "JP4") (pin "5") (pinfunction "5_5") (pintype "passive"))
    )
    (net (code "45") (name "LED_CH_D_OUT") (class "Default")
      (node (ref "IC6") (pin "10") (pinfunction "O7_10") (pintype "open_collector"))
      (node (ref "R102") (pin "2") (pinfunction "2_2") (pintype "passive"))
    )
    (net (code "46") (name "LED_CH_E_IN") (class "Default")
      (node (ref "IC7") (pin "1") (pinfunction "I1_1") (pintype "input"))
      (node (ref "JP5") (pin "2") (pinfunction "2_2") (pintype "passive"))
    )
    (net (code "47") (name "LED_CH_F_IN") (class "Default")
      (node (ref "IC7") (pin "2") (pinfunction "I2_2") (pintype "input"))
      (node (ref "JP5") (pin "5") (pinfunction "5_5") (pintype "passive"))
    )
    (net (code "48") (name "LED_CH_G_IN") (class "Default")
      (node (ref "IC7") (pin "3") (pinfunction "I3_3") (pintype "input"))
      (node (ref "JP6") (pin "2") (pinfunction "2_2") (pintype "passive"))
    )
    (net (code "49") (name "LED_CH_H_IN") (class "Default")
      (node (ref "IC7") (pin "4") (pinfunction "I4_4") (pintype "input"))
      (node (ref "JP6") (pin "5") (pinfunction "5_5") (pintype "passive"))
    )
    (net (code "50") (name "MOTOR_A_IN") (class "Default")
      (node (ref "JP7") (pin "1") (pinfunction "1_1") (pintype "passive"))
      (node (ref "R1") (pin "1") (pinfunction "1_1") (pintype "passive"))
    )
    (net (code "51") (name "MOTOR_B_IN") (class "Default")
      (node (ref "JP7") (pin "6") (pinfunction "6_6") (pintype "passive"))
      (node (ref "R2") (pin "1") (pinfunction "1_1") (pintype "passive"))
    )
    (net (code "52") (name "Net-(C1-Pad2)") (class "Default")
      (node (ref "C1") (pin "2") (pinfunction "2_2") (pintype "passive"))
      (node (ref "D13") (pin "C") (pinfunction "C_C") (pintype "passive"))
      (node (ref "U$4") (pin "V_IN") (pinfunction "V_IN_V_IN") (pintype "bidirectional"))
      (node (ref "U$7") (pin "COM") (pinfunction "COM_COM") (pintype "bidirectional"))
    )
    (net (code "53") (name "Net-(D1-PadC)") (class "Default")
      (node (ref "D1") (pin "C") (pinfunction "C_C") (pintype "passive"))
      (node (ref "U$5") (pin "11") (pinfunction "11_11") (pintype "bidirectional"))
    )
    (net (code "54") (name "Net-(D2-PadC)") (class "Default")
      (node (ref "D2") (pin "C") (pinfunction "C_C") (pintype "passive"))
      (node (ref "U$5") (pin "12") (pinfunction "12_12") (pintype "bidirectional"))
    )
    (net (code "55") (name "Net-(D3-PadC)") (class "Default")
      (node (ref "D3") (pin "C") (pinfunction "C_C") (pintype "passive"))
      (node (ref "U$5") (pin "13") (pinfunction "13_13") (pintype "bidirectional"))
    )
    (net (code "56") (name "Net-(D4-PadC)") (class "Default")
      (node (ref "D4") (pin "C") (pinfunction "C_C") (pintype "passive"))
      (node (ref "U$5") (pin "14") (pinfunction "14_14") (pintype "bidirectional"))
    )
    (net (code "57") (name "Net-(D5-PadC)") (class "Default")
      (node (ref "D5") (pin "C") (pinfunction "C_C") (pintype "passive"))
      (node (ref "U$5") (pin "15") (pinfunction "15_15") (pintype "bidirectional"))
    )
    (net (code "58") (name "Net-(D6-PadC)") (class "Default")
      (node (ref "D6") (pin "C") (pinfunction "C_C") (pintype "passive"))
      (node (ref "U$5") (pin "16") (pinfunction "16_16") (pintype "bidirectional"))
    )
    (net (code "59") (name "Net-(D7-PadC)") (class "Default")
      (node (ref "D7") (pin "C") (pinfunction "C_C") (pintype "passive"))
      (node (ref "U$6") (pin "11") (pinfunction "11_11") (pintype "bidirectional"))
    )
    (net (code "60") (name "Net-(D8-PadC)") (class "Default")
      (node (ref "D8") (pin "C") (pinfunction "C_C") (pintype "passive"))
      (node (ref "U$6") (pin "12") (pinfunction "12_12") (pintype "bidirectional"))
    )
    (net (code "61") (name "Net-(D9-PadC)") (class "Default")
      (node (ref "D9") (pin "C") (pinfunction "C_C") (pintype "passive"))
      (node (ref "U$6") (pin "13") (pinfunction "13_13") (pintype "bidirectional"))
    )
    (net (code "62") (name "Net-(D10-PadC)") (class "Default")
      (node (ref "D10") (pin "C") (pinfunction "C_C") (pintype "passive"))
      (node (ref "U$6") (pin "14") (pinfunction "14_14") (pintype "bidirectional"))
    )
    (net (code "63") (name "Net-(D11-PadC)") (class "Default")
      (node (ref "D11") (pin "C") (pinfunction "C_C") (pintype "passive"))
      (node (ref "U$6") (pin "15") (pinfunction "15_15") (pintype "bidirectional"))
    )
    (net (code "64") (name "Net-(D12-PadC)") (class "Default")
      (node (ref "D12") (pin "C") (pinfunction "C_C") (pintype "passive"))
      (node (ref "U$6") (pin "16") (pinfunction "16_16") (pintype "bidirectional"))
    )
    (net (code "65") (name "Net-(D13-PadA)") (class "Default")
      (node (ref "D13") (pin "A") (pinfunction "A_A") (pintype "passive"))
      (node (ref "JP8") (pin "1") (pinfunction "1_1") (pintype "passive"))
    )
    (net (code "66") (name "Net-(D15-PadC)") (class "Default")
      (node (ref "D15") (pin "C") (pinfunction "C_C") (pintype "passive"))
      (node (ref "U$9") (pin "11") (pinfunction "11_11") (pintype "bidirectional"))
    )
    (net (code "67") (name "Net-(D16-PadC)") (class "Default")
      (node (ref "D16") (pin "C") (pinfunction "C_C") (pintype "passive"))
      (node (ref "U$9") (pin "12") (pinfunction "12_12") (pintype "bidirectional"))
    )
    (net (code "68") (name "Net-(D17-PadC)") (class "Default")
      (node (ref "D17") (pin "C") (pinfunction "C_C") (pintype "passive"))
      (node (ref "U$9") (pin "13") (pinfunction "13_13") (pintype "bidirectional"))
    )
    (net (code "69") (name "Net-(D18-PadC)") (class "Default")
      (node (ref "D18") (pin "C") (pinfunction "C_C") (pintype "passive"))
      (node (ref "U$9") (pin "14") (pinfunction "14_14") (pintype "bidirectional"))
    )
    (net (code "70") (name "Net-(D19-PadC)") (class "Default")
      (node (ref "D19") (pin "C") (pinfunction "C_C") (pintype "passive"))
      (node (ref "U$9") (pin "15") (pinfunction "15_15") (pintype "bidirectional"))
    )
    (net (code "71") (name "Net-(D20-PadC)") (class "Default")
      (node (ref "D20") (pin "C") (pinfunction "C_C") (pintype "passive"))
      (node (ref "U$9") (pin "16") (pinfunction "16_16") (pintype "bidirectional"))
    )
    (net (code "72") (name "Net-(D21-PadC)") (class "Default")
      (node (ref "D21") (pin "C") (pinfunction "C_C") (pintype "passive"))
      (node (ref "U$10") (pin "11") (pinfunction "11_11") (pintype "bidirectional"))
    )
    (net (code "73") (name "Net-(D22-PadC)") (class "Default")
      (node (ref "D22") (pin "C") (pinfunction "C_C") (pintype "passive"))
      (node (ref "U$10") (pin "12") (pinfunction "12_12") (pintype "bidirectional"))
    )
    (net (code "74") (name "Net-(D23-PadC)") (class "Default")
      (node (ref "D23") (pin "C") (pinfunction "C_C") (pintype "passive"))
      (node (ref "U$10") (pin "13") (pinfunction "13_13") (pintype "bidirectional"))
    )
    (net (code "75") (name "Net-(D24-PadC)") (class "Default")
      (node (ref "D24") (pin "C") (pinfunction "C_C") (pintype "passive"))
      (node (ref "U$10") (pin "14") (pinfunction "14_14") (pintype "bidirectional"))
    )
    (net (code "76") (name "Net-(D25-PadC)") (class "Default")
      (node (ref "D25") (pin "C") (pinfunction "C_C") (pintype "passive"))
      (node (ref "U$10") (pin "15") (pinfunction "15_15") (pintype "bidirectional"))
    )
    (net (code "77") (name "Net-(D26-PadC)") (class "Default")
      (node (ref "D26") (pin "C") (pinfunction "C_C") (pintype "passive"))
      (node (ref "U$10") (pin "16") (pinfunction "16_16") (pintype "bidirectional"))
    )
    (net (code "78") (name "Net-(IC2-O1)") (class "Default")
      (node (ref "IC2") (pin "16") (pinfunction "O1_16") (pintype "open_collector"))
      (node (ref "U$5") (pin "1") (pinfunction "1_1") (pintype "bidirectional"))
    )
    (net (code "79") (name "Net-(IC2-O2)") (class "Default")
      (node (ref "IC2") (pin "15") (pinfunction "O2_15") (pintype "open_collector"))
      (node (ref "U$5") (pin "2") (pinfunction "2_2") (pintype "bidirectional"))
    )
    (net (code "80") (name "Net-(IC2-O3)") (class "Default")
      (node (ref "IC2") (pin "14") (pinfunction "O3_14") (pintype "open_collector"))
      (node (ref "U$5") (pin "3") (pinfunction "3_3") (pintype "bidirectional"))
    )
    (net (code "81") (name "Net-(IC2-O4)") (class "Default")
      (node (ref "IC2") (pin "13") (pinfunction "O4_13") (pintype "open_collector"))
      (node (ref "U$5") (pin "4") (pinfunction "4_4") (pintype "bidirectional"))
    )
    (net (code "82") (name "Net-(IC2-O5)") (class "Default")
      (node (ref "IC2") (pin "12") (pinfunction "O5_12") (pintype "open_collector"))
      (node (ref "U$5") (pin "5") (pinfunction "5_5") (pintype "bidirectional"))
    )
    (net (code "83") (name "Net-(IC2-O6)") (class "Default")
      (node (ref "IC2") (pin "11") (pinfunction "O6_11") (pintype "open_collector"))
      (node (ref "U$5") (pin "6") (pinfunction "6_6") (pintype "bidirectional"))
    )
    (net (code "84") (name "Net-(IC4-O1)") (class "Default")
      (node (ref "IC4") (pin "16") (pinfunction "O1_16") (pintype "open_collector"))
      (node (ref "U$6") (pin "1") (pinfunction "1_1") (pintype "bidirectional"))
    )
    (net (code "85") (name "Net-(IC4-O2)") (class "Default")
      (node (ref "IC4") (pin "15") (pinfunction "O2_15") (pintype "open_collector"))
      (node (ref "U$6") (pin "2") (pinfunction "2_2") (pintype "bidirectional"))
    )
    (net (code "86") (name "Net-(IC4-O3)") (class "Default")
      (node (ref "IC4") (pin "14") (pinfunction "O3_14") (pintype "open_collector"))
      (node (ref "U$6") (pin "3") (pinfunction "3_3") (pintype "bidirectional"))
    )
    (net (code "87") (name "Net-(IC4-O4)") (class "Default")
      (node (ref "IC4") (pin "13") (pinfunction "O4_13") (pintype "open_collector"))
      (node (ref "U$6") (pin "4") (pinfunction "4_4") (pintype "bidirectional"))
    )
    (net (code "88") (name "Net-(IC4-O5)") (class "Default")
      (node (ref "IC4") (pin "12") (pinfunction "O5_12") (pintype "open_collector"))
      (node (ref "U$6") (pin "5") (pinfunction "5_5") (pintype "bidirectional"))
    )
    (net (code "89") (name "Net-(IC4-O6)") (class "Default")
      (node (ref "IC4") (pin "11") (pinfunction "O6_11") (pintype "open_collector"))
      (node (ref "U$6") (pin "6") (pinfunction "6_6") (pintype "bidirectional"))
    )
    (net (code "90") (name "Net-(IC5-O1)") (class "Default")
      (node (ref "IC5") (pin "16") (pinfunction "O1_16") (pintype "open_collector"))
      (node (ref "U$9") (pin "1") (pinfunction "1_1") (pintype "bidirectional"))
    )
    (net (code "91") (name "Net-(IC5-O2)") (class "Default")
      (node (ref "IC5") (pin "15") (pinfunction "O2_15") (pintype "open_collector"))
      (node (ref "U$9") (pin "2") (pinfunction "2_2") (pintype "bidirectional"))
    )
    (net (code "92") (name "Net-(IC5-O3)") (class "Default")
      (node (ref "IC5") (pin "14") (pinfunction "O3_14") (pintype "open_collector"))
      (node (ref "U$9") (pin "3") (pinfunction "3_3") (pintype "bidirectional"))
    )
    (net (code "93") (name "Net-(IC5-O4)") (class "Default")
      (node (ref "IC5") (pin "13") (pinfunction "O4_13") (pintype "open_collector"))
      (node (ref "U$9") (pin "4") (pinfunction "4_4") (pintype "bidirectional"))
    )
    (net (code "94") (name "Net-(IC5-O5)") (class "Default")
      (node (ref "IC5") (pin "12") (pinfunction "O5_12") (pintype "open_collector"))
      (node (ref "U$9") (pin "5") (pinfunction "5_5") (pintype "bidirectional"))
    )
    (net (code "95") (name "Net-(IC5-O6)") (class "Default")
      (node (ref "IC5") (pin "11") (pinfunction "O6_11") (pintype "open_collector"))
      (node (ref "U$9") (pin "6") (pinfunction "6_6") (pintype "bidirectional"))
    )
    (net (code "96") (name "Net-(IC6-O1)") (class "Default")
      (node (ref "IC6") (pin "16") (pinfunction "O1_16") (pintype "open_collector"))
      (node (ref "U$10") (pin "1") (pinfunction "1_1") (pintype "bidirectional"))
    )
    (net (code "97") (name "Net-(IC6-O2)") (class "Default")
      (node (ref "IC6") (pin "15") (pinfunction "O2_15") (pintype "open_collector"))
      (node (ref "U$10") (pin "2") (pinfunction "2_2") (pintype "bidirectional"))
    )
    (net (code "98") (name "Net-(IC6-O3)") (class "Default")
      (node (ref "IC6") (pin "14") (pinfunction "O3_14") (pintype "open_collector"))
      (node (ref "U$10") (pin "3") (pinfunction "3_3") (pintype "bidirectional"))
    )
    (net (code "99") (name "Net-(IC6-O4)") (class "Default")
      (node (ref "IC6") (pin "13") (pinfunction "O4_13") (pintype "open_collector"))
      (node (ref "U$10") (pin "4") (pinfunction "4_4") (pintype "bidirectional"))
    )
    (net (code "100") (name "Net-(IC6-O5)") (class "Default")
      (node (ref "IC6") (pin "12") (pinfunction "O5_12") (pintype "open_collector"))
      (node (ref "U$10") (pin "5") (pinfunction "5_5") (pintype "bidirectional"))
    )
    (net (code "101") (name "Net-(IC6-O6)") (class "Default")
      (node (ref "IC6") (pin "11") (pinfunction "O6_11") (pintype "open_collector"))
      (node (ref "U$10") (pin "6") (pinfunction "6_6") (pintype "bidirectional"))
    )
    (net (code "102") (name "Net-(IC7-O1)") (class "Default")
      (node (ref "IC7") (pin "16") (pinfunction "O1_16") (pintype "open_collector"))
      (node (ref "R111") (pin "2") (pinfunction "2_2") (pintype "passive"))
    )
    (net (code "103") (name "Net-(IC7-O2)") (class "Default")
      (node (ref "IC7") (pin "15") (pinfunction "O2_15") (pintype "open_collector"))
      (node (ref "R112") (pin "2") (pinfunction "2_2") (pintype "passive"))
    )
    (net (code "104") (name "Net-(IC7-O3)") (class "Default")
      (node (ref "IC7") (pin "14") (pinfunction "O3_14") (pintype "open_collector"))
      (node (ref "R113") (pin "2") (pinfunction "2_2") (pintype "passive"))
    )
    (net (code "105") (name "Net-(IC7-O4)") (class "Default")
      (node (ref "IC7") (pin "13") (pinfunction "O4_13") (pintype "open_collector"))
      (node (ref "R114") (pin "2") (pinfunction "2_2") (pintype "passive"))
    )
    (net (code "106") (name "Net-(LED_A-C)") (class "Default")
      (node (ref "LED_A") (pin "K") (pinfunction "C_K") (pintype "passive"))
      (node (ref "R99") (pin "1") (pinfunction "1_1") (pintype "passive"))
    )
    (net (code "107") (name "Net-(LED_B-C)") (class "Default")
      (node (ref "LED_B") (pin "K") (pinfunction "C_K") (pintype "passive"))
      (node (ref "R100") (pin "1") (pinfunction "1_1") (pintype "passive"))
    )
    (net (code "108") (name "Net-(LED_C-C)") (class "Default")
      (node (ref "LED_C") (pin "K") (pinfunction "C_K") (pintype "passive"))
      (node (ref "R101") (pin "1") (pinfunction "1_1") (pintype "passive"))
    )
    (net (code "109") (name "Net-(LED_D-C)") (class "Default")
      (node (ref "LED_D") (pin "K") (pinfunction "C_K") (pintype "passive"))
      (node (ref "R102") (pin "1") (pinfunction "1_1") (pintype "passive"))
    )
    (net (code "110") (name "Net-(LED_E-C)") (class "Default")
      (node (ref "LED_E") (pin "K") (pinfunction "C_K") (pintype "passive"))
      (node (ref "R111") (pin "1") (pinfunction "1_1") (pintype "passive"))
    )
    (net (code "111") (name "Net-(LED_F-C)") (class "Default")
      (node (ref "LED_F") (pin "K") (pinfunction "C_K") (pintype "passive"))
      (node (ref "R112") (pin "1") (pinfunction "1_1") (pintype "passive"))
    )
    (net (code "112") (name "Net-(LED_G-C)") (class "Default")
      (node (ref "LED_G") (pin "K") (pinfunction "C_K") (pintype "passive"))
      (node (ref "R113") (pin "1") (pinfunction "1_1") (pintype "passive"))
    )
    (net (code "113") (name "Net-(LED_H-C)") (class "Default")
      (node (ref "LED_H") (pin "K") (pinfunction "C_K") (pintype "passive"))
      (node (ref "R114") (pin "1") (pinfunction "1_1") (pintype "passive"))
    )
    (net (code "114") (name "Net-(LED_IR_A-C)") (class "Default")
      (node (ref "LED_IR_A") (pin "K") (pinfunction "C_K") (pintype "passive"))
      (node (ref "R12") (pin "1") (pinfunction "1_1") (pintype "passive"))
    )
    (net (code "115") (name "Net-(LED_IR_B-C)") (class "Default")
      (node (ref "LED_IR_B") (pin "K") (pinfunction "C_K") (pintype "passive"))
      (node (ref "R13") (pin "1") (pinfunction "1_1") (pintype "passive"))
    )
    (net (code "116") (name "Net-(Q1-D-Pad5)") (class "Default")
      (node (ref "Q1") (pin "5") (pinfunction "D_5") (pintype "passive"))
      (node (ref "Q1") (pin "6") (pinfunction "D_6") (pintype "passive"))
      (node (ref "Q1") (pin "7") (pinfunction "D_7") (pintype "passive"))
      (node (ref "Q1") (pin "8") (pinfunction "D_8") (pintype "passive"))
      (node (ref "U$1") (pin "P$1") (pinfunction "P$1_P$1") (pintype "bidirectional"))
    )
    (net (code "117") (name "Net-(Q1-G)") (class "Default")
      (node (ref "Q1") (pin "4") (pinfunction "G_4") (pintype "passive"))
      (node (ref "R2") (pin "2") (pinfunction "2_2") (pintype "passive"))
      (node (ref "R3") (pin "2") (pinfunction "2_2") (pintype "passive"))
    )
    (net (code "118") (name "Net-(Q2-D-Pad5)") (class "Default")
      (node (ref "Q2") (pin "5") (pinfunction "D_5") (pintype "passive"))
      (node (ref "Q2") (pin "6") (pinfunction "D_6") (pintype "passive"))
      (node (ref "Q2") (pin "7") (pinfunction "D_7") (pintype "passive"))
      (node (ref "Q2") (pin "8") (pinfunction "D_8") (pintype "passive"))
      (node (ref "U$2") (pin "P$1") (pinfunction "P$1_P$1") (pintype "bidirectional"))
    )
    (net (code "119") (name "Net-(Q2-G)") (class "Default")
      (node (ref "Q2") (pin "4") (pinfunction "G_4") (pintype "passive"))
      (node (ref "R1") (pin "2") (pinfunction "2_2") (pintype "passive"))
      (node (ref "R4") (pin "2") (pinfunction "2_2") (pintype "passive"))
    )
    (net (code "120") (name "Net-(R5-Pad2)") (class "Default")
      (node (ref "R5") (pin "2") (pinfunction "2_2") (pintype "passive"))
      (node (ref "U$12") (pin "1") (pinfunction "1_1") (pintype "passive"))
    )
    (net (code "121") (name "Net-(R6-Pad2)") (class "Default")
      (node (ref "R6") (pin "2") (pinfunction "2_2") (pintype "passive"))
      (node (ref "U$13") (pin "1") (pinfunction "1_1") (pintype "passive"))
    )
    (net (code "122") (name "Net-(R7-Pad2)") (class "Default")
      (node (ref "R7") (pin "2") (pinfunction "2_2") (pintype "passive"))
      (node (ref "U$14") (pin "1") (pinfunction "1_1") (pintype "passive"))
    )
    (net (code "123") (name "Net-(R8-Pad2)") (class "Default")
      (node (ref "R8") (pin "2") (pinfunction "2_2") (pintype "passive"))
      (node (ref "U$15") (pin "1") (pinfunction "1_1") (pintype "passive"))
    )
    (net (code "124") (name "Net-(R9-Pad2)") (class "Default")
      (node (ref "R9") (pin "2") (pinfunction "2_2") (pintype "passive"))
      (node (ref "U$16") (pin "1") (pinfunction "1_1") (pintype "passive"))
    )
    (net (code "125") (name "Net-(R10-Pad2)") (class "Default")
      (node (ref "R10") (pin "2") (pinfunction "2_2") (pintype "passive"))
      (node (ref "U$17") (pin "1") (pinfunction "1_1") (pintype "passive"))
    )
    (net (code "126") (name "Net-(R11-Pad2)") (class "Default")
      (node (ref "R11") (pin "2") (pinfunction "2_2") (pintype "passive"))
      (node (ref "U$18") (pin "1") (pinfunction "1_1") (pintype "passive"))
    )
    (net (code "127") (name "Net-(R39-Pad2)") (class "Default")
      (node (ref "R39") (pin "2") (pinfunction "2_2") (pintype "passive"))
      (node (ref "U$8") (pin "1") (pinfunction "1_1") (pintype "passive"))
    )
    (net (code "128") (name "Net-(U$4-PadEN)") (class "Default")
      (node (ref "U$4") (pin "EN") (pinfunction "EN_EN") (pintype "bidirectional"))
      (node (ref "U$7") (pin "NC") (pinfunction "NC_NC") (pintype "bidirectional"))
    )
    (net (code "129") (name "VDD") (class "Default")
      (node (ref "C2") (pin "2") (pinfunction "2_2") (pintype "passive"))
      (node (ref "D1") (pin "A") (pinfunction "A_A") (pintype "passive"))
      (node (ref "D10") (pin "A") (pinfunction "A_A") (pintype "passive"))
      (node (ref "D11") (pin "A") (pinfunction "A_A") (pintype "passive"))
      (node (ref "D12") (pin "A") (pinfunction "A_A") (pintype "passive"))
      (node (ref "D15") (pin "A") (pinfunction "A_A") (pintype "passive"))
      (node (ref "D16") (pin "A") (pinfunction "A_A") (pintype "passive"))
      (node (ref "D17") (pin "A") (pinfunction "A_A") (pintype "passive"))
      (node (ref "D18") (pin "A") (pinfunction "A_A") (pintype "passive"))
      (node (ref "D19") (pin "A") (pinfunction "A_A") (pintype "passive"))
      (node (ref "D2") (pin "A") (pinfunction "A_A") (pintype "passive"))
      (node (ref "D20") (pin "A") (pinfunction "A_A") (pintype "passive"))
      (node (ref "D21") (pin "A") (pinfunction "A_A") (pintype "passive"))
      (node (ref "D22") (pin "A") (pinfunction "A_A") (pintype "passive"))
      (node (ref "D23") (pin "A") (pinfunction "A_A") (pintype "passive"))
      (node (ref "D24") (pin "A") (pinfunction "A_A") (pintype "passive"))
      (node (ref "D25") (pin "A") (pinfunction "A_A") (pintype "passive"))
      (node (ref "D26") (pin "A") (pinfunction "A_A") (pintype "passive"))
      (node (ref "D3") (pin "A") (pinfunction "A_A") (pintype "passive"))
      (node (ref "D4") (pin "A") (pinfunction "A_A") (pintype "passive"))
      (node (ref "D5") (pin "A") (pinfunction "A_A") (pintype "passive"))
      (node (ref "D6") (pin "A") (pinfunction "A_A") (pintype "passive"))
      (node (ref "D7") (pin "A") (pinfunction "A_A") (pintype "passive"))
      (node (ref "D8") (pin "A") (pinfunction "A_A") (pintype "passive"))
      (node (ref "D9") (pin "A") (pinfunction "A_A") (pintype "passive"))
      (node (ref "IC1") (pin "14") (pinfunction "VDD_14") (pintype "power_in"))
      (node (ref "IC2") (pin "9") (pinfunction "CD+_9") (pintype "passive"))
      (node (ref "IC3") (pin "14") (pinfunction "VDD_14") (pintype "power_in"))
      (node (ref "IC4") (pin "9") (pinfunction "CD+_9") (pintype "passive"))
      (node (ref "IC5") (pin "9") (pinfunction "CD+_9") (pintype "passive"))
      (node (ref "IC6") (pin "9") (pinfunction "CD+_9") (pintype "passive"))
      (node (ref "IC7") (pin "9") (pinfunction "CD+_9") (pintype "passive"))
      (node (ref "JP3") (pin "1") (pinfunction "1_1") (pintype "passive"))
      (node (ref "JP3") (pin "6") (pinfunction "6_6") (pintype "passive"))
      (node (ref "JP4") (pin "1") (pinfunction "1_1") (pintype "passive"))
      (node (ref "JP4") (pin "6") (pinfunction "6_6") (pintype "passive"))
      (node (ref "JP5") (pin "1") (pinfunction "1_1") (pintype "passive"))
      (node (ref "JP5") (pin "6") (pinfunction "6_6") (pintype "passive"))
      (node (ref "JP6") (pin "1") (pinfunction "1_1") (pintype "passive"))
      (node (ref "JP6") (pin "6") (pinfunction "6_6") (pintype "passive"))
      (node (ref "LDR_A") (pin "1") (pinfunction "1_1") (pintype "passive"))
      (node (ref "LDR_B") (pin "1") (pinfunction "1_1") (pintype "passive"))
      (node (ref "LDR_C") (pin "1") (pinfunction "1_1") (pintype "passive"))
      (node (ref "LDR_D") (pin "1") (pinfunction "1_1") (pintype "passive"))
      (node (ref "LDR_E") (pin "1") (pinfunction "1_1") (pintype "passive"))
      (node (ref "LDR_F") (pin "1") (pinfunction "1_1") (pintype "passive"))
      (node (ref "LDR_G") (pin "1") (pinfunction "1_1") (pintype "passive"))
      (node (ref "LDR_H") (pin "1") (pinfunction "1_1") (pintype "passive"))
      (node (ref "LDR_PRO_A_IN2") (pin "2") (pinfunction "2_2") (pintype "passive"))
      (node (ref "LDR_PRO_B_IN2") (pin "2") (pinfunction "2_2") (pintype "passive"))
      (node (ref "LDR_PRO_C_IN2") (pin "2") (pinfunction "2_2") (pintype "passive"))
      (node (ref "LDR_PRO_D_IN2") (pin "2") (pinfunction "2_2") (pintype "passive"))
      (node (ref "LED_A") (pin "A") (pinfunction "A_A") (pintype "passive"))
      (node (ref "LED_B") (pin "A") (pinfunction "A_A") (pintype "passive"))
      (node (ref "LED_C") (pin "A") (pinfunction "A_A") (pintype "passive"))
      (node (ref "LED_D") (pin "A") (pinfunction "A_A") (pintype "passive"))
      (node (ref "LED_E") (pin "A") (pinfunction "A_A") (pintype "passive"))
      (node (ref "LED_F") (pin "A") (pinfunction "A_A") (pintype "passive"))
      (node (ref "LED_G") (pin "A") (pinfunction "A_A") (pintype "passive"))
      (node (ref "LED_H") (pin "A") (pinfunction "A_A") (pintype "passive"))
      (node (ref "LED_IR_A") (pin "A") (pinfunction "A_A") (pintype "passive"))
      (node (ref "LED_IR_B") (pin "A") (pinfunction "A_A") (pintype "passive"))
      (node (ref "U$1") (pin "P$2") (pinfunction "P$2_P$2") (pintype "bidirectional"))
      (node (ref "U$2") (pin "P$2") (pinfunction "P$2_P$2") (pintype "bidirectional"))
      (node (ref "U$4") (pin "V_OUT") (pinfunction "V_OUT_V_OUT") (pintype "bidirectional"))
      (node (ref "U$4") (pin "V_OUT_MON") (pinfunction "V_OUT_MON_V_OUT_MON") (pintype "bidirectional"))
    )
    (net (code "130") (name "unconnected-(IC7-I5-Pad5)") (class "Default")
      (node (ref "IC7") (pin "5") (pinfunction "I5_5") (pintype "input"))
    )
    (net (code "131") (name "unconnected-(IC7-I6-Pad6)") (class "Default")
      (node (ref "IC7") (pin "6") (pinfunction "I6_6") (pintype "input"))
    )
    (net (code "132") (name "unconnected-(IC7-I7-Pad7)") (class "Default")
      (node (ref "IC7") (pin "7") (pinfunction "I7_7") (pintype "input"))
    )
    (net (code "133") (name "unconnected-(IC7-O5-Pad12)") (class "Default")
      (node (ref "IC7") (pin "12") (pinfunction "O5_12") (pintype "open_collector"))
    )
    (net (code "134") (name "unconnected-(IC7-O6-Pad11)") (class "Default")
      (node (ref "IC7") (pin "11") (pinfunction "O6_11") (pintype "open_collector"))
    )
    (net (code "135") (name "unconnected-(IC7-O7-Pad10)") (class "Default")
      (node (ref "IC7") (pin "10") (pinfunction "O7_10") (pintype "open_collector"))
    )
    (net (code "136") (name "unconnected-(U$3-Pad13)") (class "Default")
      (node (ref "U$3") (pin "13") (pinfunction "13_13") (pintype "bidirectional"))
    )
    (net (code "137") (name "unconnected-(U$3-Pad14)") (class "Default")
      (node (ref "U$3") (pin "14") (pinfunction "14_14") (pintype "bidirectional"))
    )
    (net (code "138") (name "unconnected-(U$3-Pad15)") (class "Default")
      (node (ref "U$3") (pin "15") (pinfunction "15_15") (pintype "bidirectional"))
    )
    (net (code "139") (name "unconnected-(U$5-Pad7)") (class "Default")
      (node (ref "U$5") (pin "7") (pinfunction "7_7") (pintype "bidirectional"))
    )
    (net (code "140") (name "unconnected-(U$5-Pad8)") (class "Default")
      (node (ref "U$5") (pin "8") (pinfunction "8_8") (pintype "bidirectional"))
    )
    (net (code "141") (name "unconnected-(U$5-Pad9)") (class "Default")
      (node (ref "U$5") (pin "9") (pinfunction "9_9") (pintype "bidirectional"))
    )
    (net (code "142") (name "unconnected-(U$5-Pad10)") (class "Default")
      (node (ref "U$5") (pin "10") (pinfunction "10_10") (pintype "bidirectional"))
    )
    (net (code "143") (name "unconnected-(U$6-Pad7)") (class "Default")
      (node (ref "U$6") (pin "7") (pinfunction "7_7") (pintype "bidirectional"))
    )
    (net (code "144") (name "unconnected-(U$6-Pad8)") (class "Default")
      (node (ref "U$6") (pin "8") (pinfunction "8_8") (pintype "bidirectional"))
    )
    (net (code "145") (name "unconnected-(U$6-Pad9)") (class "Default")
      (node (ref "U$6") (pin "9") (pinfunction "9_9") (pintype "bidirectional"))
    )
    (net (code "146") (name "unconnected-(U$6-Pad10)") (class "Default")
      (node (ref "U$6") (pin "10") (pinfunction "10_10") (pintype "bidirectional"))
    )
    (net (code "147") (name "unconnected-(U$7-PadNO)") (class "Default")
      (node (ref "U$7") (pin "NO") (pinfunction "NO_NO") (pintype "bidirectional"))
    )
    (net (code "148") (name "unconnected-(U$8-Pad3)") (class "Default")
      (node (ref "U$8") (pin "3") (pinfunction "3_3") (pintype "passive"))
    )
    (net (code "149") (name "unconnected-(U$9-Pad7)") (class "Default")
      (node (ref "U$9") (pin "7") (pinfunction "7_7") (pintype "bidirectional"))
    )
    (net (code "150") (name "unconnected-(U$9-Pad8)") (class "Default")
      (node (ref "U$9") (pin "8") (pinfunction "8_8") (pintype "bidirectional"))
    )
    (net (code "151") (name "unconnected-(U$9-Pad9)") (class "Default")
      (node (ref "U$9") (pin "9") (pinfunction "9_9") (pintype "bidirectional"))
    )
    (net (code "152") (name "unconnected-(U$9-Pad10)") (class "Default")
      (node (ref "U$9") (pin "10") (pinfunction "10_10") (pintype "bidirectional"))
    )
    (net (code "153") (name "unconnected-(U$10-Pad7)") (class "Default")
      (node (ref "U$10") (pin "7") (pinfunction "7_7") (pintype "bidirectional"))
    )
    (net (code "154") (name "unconnected-(U$10-Pad8)") (class "Default")
      (node (ref "U$10") (pin "8") (pinfunction "8_8") (pintype "bidirectional"))
    )
    (net (code "155") (name "unconnected-(U$10-Pad9)") (class "Default")
      (node (ref "U$10") (pin "9") (pinfunction "9_9") (pintype "bidirectional"))
    )
    (net (code "156") (name "unconnected-(U$10-Pad10)") (class "Default")
      (node (ref "U$10") (pin "10") (pinfunction "10_10") (pintype "bidirectional"))
    )
    (net (code "157") (name "unconnected-(U$11-Pad13)") (class "Default")
      (node (ref "U$11") (pin "13") (pinfunction "13_13") (pintype "bidirectional"))
    )
    (net (code "158") (name "unconnected-(U$11-Pad14)") (class "Default")
      (node (ref "U$11") (pin "14") (pinfunction "14_14") (pintype "bidirectional"))
    )
    (net (code "159") (name "unconnected-(U$11-Pad15)") (class "Default")
      (node (ref "U$11") (pin "15") (pinfunction "15_15") (pintype "bidirectional"))
    )
    (net (code "160") (name "unconnected-(U$12-Pad3)") (class "Default")
      (node (ref "U$12") (pin "3") (pinfunction "3_3") (pintype "passive"))
    )
    (net (code "161") (name "unconnected-(U$13-Pad3)") (class "Default")
      (node (ref "U$13") (pin "3") (pinfunction "3_3") (pintype "passive"))
    )
    (net (code "162") (name "unconnected-(U$14-Pad3)") (class "Default")
      (node (ref "U$14") (pin "3") (pinfunction "3_3") (pintype "passive"))
    )
    (net (code "163") (name "unconnected-(U$15-Pad3)") (class "Default")
      (node (ref "U$15") (pin "3") (pinfunction "3_3") (pintype "passive"))
    )
    (net (code "164") (name "unconnected-(U$16-Pad3)") (class "Default")
      (node (ref "U$16") (pin "3") (pinfunction "3_3") (pintype "passive"))
    )
    (net (code "165") (name "unconnected-(U$17-Pad3)") (class "Default")
      (node (ref "U$17") (pin "3") (pinfunction "3_3") (pintype "passive"))
    )
    (net (code "166") (name "unconnected-(U$18-Pad3)") (class "Default")
      (node (ref "U$18") (pin "3") (pinfunction "3_3") (pintype "passive"))
    )
  )
)
